# Sheet11.net
KiCad netlist of a schematic drawn in Altium Designer
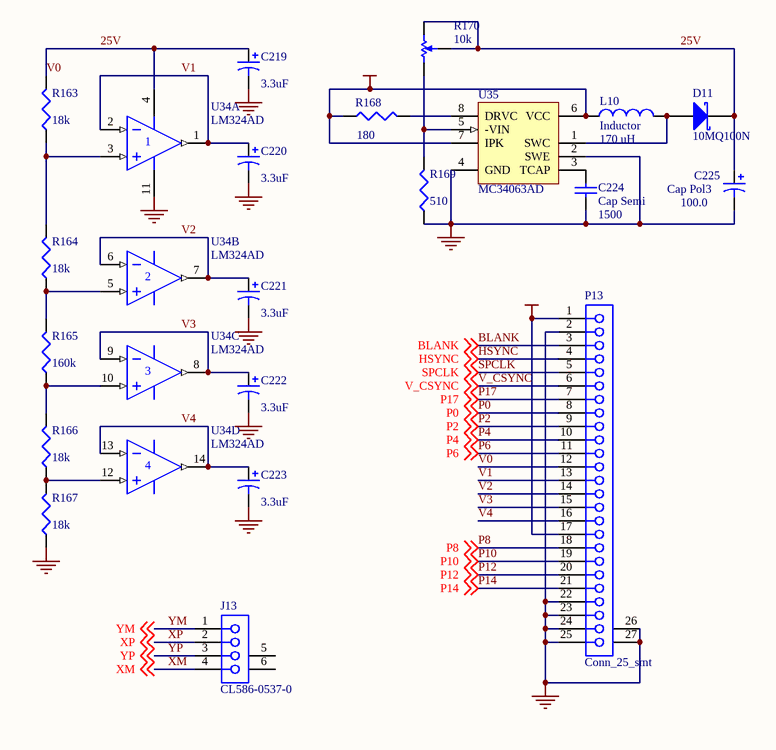
[diagram p0: Sheet11.SchDoc]

(export (version "E")
  (design (tool "Eeschema 10.0.6"))
  (components
    (comp (ref "C219")
      (value "3.3uF")
      (footprint "CC2012-0805")
      (description "Polarized Capacitor (Surface Mount)")
      (fields (field (name "Comment") "Cap Pol3") (field (name "PUBLISHER") "Altium Limited"))
      (libsource (lib "Miscellaneous Devices") (part "Cap Pol3"))
    )
    (comp (ref "C220")
      (value "3.3uF")
      (footprint "CC2012-0805")
      (description "Polarized Capacitor (Surface Mount)")
      (fields (field (name "Comment") "Cap Pol3") (field (name "PUBLISHER") "Altium Limited"))
      (libsource (lib "Miscellaneous Devices") (part "Cap Pol3"))
    )
    (comp (ref "C221")
      (value "3.3uF")
      (footprint "CC2012-0805")
      (description "Polarized Capacitor (Surface Mount)")
      (fields (field (name "Comment") "Cap Pol3") (field (name "PUBLISHER") "Altium Limited"))
      (libsource (lib "Miscellaneous Devices") (part "Cap Pol3"))
    )
    (comp (ref "C222")
      (value "3.3uF")
      (footprint "CC2012-0805")
      (description "Polarized Capacitor (Surface Mount)")
      (fields (field (name "Comment") "Cap Pol3") (field (name "PUBLISHER") "Altium Limited"))
      (libsource (lib "Miscellaneous Devices") (part "Cap Pol3"))
    )
    (comp (ref "C223")
      (value "3.3uF")
      (footprint "CC2012-0805")
      (description "Polarized Capacitor (Surface Mount)")
      (fields (field (name "Comment") "Cap Pol3") (field (name "PUBLISHER") "Altium Limited"))
      (libsource (lib "Miscellaneous Devices") (part "Cap Pol3"))
    )
    (comp (ref "C224")
      (value "Cap Semi")
      (footprint "CC1608-0603")
      (description "Capacitor (Semiconductor SIM Model)")
      (fields (field (name "ALTIUM_VALUE") "1500") (field (name "PUBLISHER") "Altium Limited"))
      (libsource (lib "Miscellaneous Devices") (part "Cap Semi"))
    )
    (comp (ref "C225")
      (value "Cap Pol3")
      (footprint "CC5664-2225")
      (description "Polarized Capacitor (Surface Mount)")
      (fields (field (name "ALTIUM_VALUE") "100.0") (field (name "PUBLISHER") "Altium Limited"))
      (libsource (lib "Miscellaneous Devices") (part "Cap Pol3"))
    )
    (comp (ref "D11")
      (value "10MQ100N")
      (footprint "CD4532-1812")
      (description "Schottky Diode")
      (fields (field (name "PUBLISHER") "Altium Limited"))
      (libsource (lib "Miscellaneous Devices") (part "D Schottky"))
    )
    (comp (ref "J13")
      (value "CL586-0537-0")
      (footprint "FH12-10(4)SA-1SH")
      (description "FH12 Series, \"Flip-Lock\" SMT/ZIF Connector - 1.0mm Spaced Bottom Eccentric Contact")
      (fields (field (name "PUBLISHER") "Altium Limited"))
      (libsource (lib "HRS FPC-FFC FH12 Series") (part "CL586-0537-0"))
    )
    (comp (ref "L10")
      (value "Inductor")
      (footprint "INDC4532-1812")
      (fields (field (name "ALTIUM_VALUE") "170 uH") (field (name "PUBLISHER") "Altium Limited"))
      (libsource (lib "Miscellaneous Devices") (part "Inductor"))
    )
    (comp (ref "P13")
      (value "Conn_25_smt")
      (footprint "Conn_25_smt")
      (libsource (lib "connectors") (part "Conn_25_smt"))
    )
    (comp (ref "R163")
      (value "18k")
      (footprint "CR1608-0603")
      (description "Resistor")
      (fields (field (name "Comment") "Res3") (field (name "PUBLISHER") "Altium Limited"))
      (libsource (lib "Miscellaneous Devices") (part "Res3"))
    )
    (comp (ref "R164")
      (value "18k")
      (footprint "CR1608-0603")
      (description "Resistor")
      (fields (field (name "Comment") "Res3") (field (name "PUBLISHER") "Altium Limited"))
      (libsource (lib "Miscellaneous Devices") (part "Res3"))
    )
    (comp (ref "R165")
      (value "160k")
      (footprint "CR1608-0603")
      (description "Resistor")
      (fields (field (name "Comment") "Res3") (field (name "PUBLISHER") "Altium Limited"))
      (libsource (lib "Miscellaneous Devices") (part "Res3"))
    )
    (comp (ref "R166")
      (value "18k")
      (footprint "CR1608-0603")
      (description "Resistor")
      (fields (field (name "Comment") "Res3") (field (name "PUBLISHER") "Altium Limited"))
      (libsource (lib "Miscellaneous Devices") (part "Res3"))
    )
    (comp (ref "R167")
      (value "18k")
      (footprint "CR1608-0603")
      (description "Resistor")
      (fields (field (name "Comment") "Res3") (field (name "PUBLISHER") "Altium Limited"))
      (libsource (lib "Miscellaneous Devices") (part "Res3"))
    )
    (comp (ref "R168")
      (value "180")
      (footprint "CR1608-0603")
      (description "Resistor")
      (fields (field (name "Comment") "Res3") (field (name "PUBLISHER") "Altium Limited"))
      (libsource (lib "Miscellaneous Devices") (part "Res3"))
    )
    (comp (ref "R169")
      (value "510")
      (footprint "CR1608-0603")
      (description "Resistor")
      (fields (field (name "Comment") "Res3") (field (name "PUBLISHER") "Altium Limited"))
      (libsource (lib "Miscellaneous Devices") (part "Res3"))
    )
    (comp (ref "R170")
      (value "10k")
      (footprint "POT4MM-2")
      (description "Square Trimming Potentiometer")
      (fields (field (name "PUBLISHER") "Altium Limited"))
      (libsource (lib "Miscellaneous Devices") (part "RPot SM"))
    )
    (comp (ref "U34")
      (value "LM324AD")
      (footprint "751A-02")
      (description "Quad Low-Power Operational Amplifier")
      (fields (field (name "PUBLISHER") "Altium Limited"))
      (libsource (lib "Motorola Amplifier Operational Amplifier") (part "LM324AD"))
    )
    (comp (ref "U35")
      (value "MC34063AD")
      (footprint "751-02")
      (description "DC-to-DC Converter Control Circuit")
      (fields (field (name "PUBLISHER") "Altium Limited"))
      (libsource (lib "Motorola Power Mgt DC-DC Converter") (part "MC34063AD"))
    )
  )
  (nets
    (net (code "1") (name "/V1") (class "Default")
      (node (ref "C220") (pin "1") (pinfunction "1_1") (pintype "passive"))
      (node (ref "P13") (pin "13") (pinfunction "13_13") (pintype "passive"))
      (node (ref "U34") (pin "1") (pinfunction "OUT_1") (pintype "output"))
      (node (ref "U34") (pin "2") (pinfunction "IN-_2") (pintype "input"))
    )
    (net (code "2") (name "/V2") (class "Default")
      (node (ref "C221") (pin "1") (pinfunction "1_1") (pintype "passive"))
      (node (ref "P13") (pin "14") (pinfunction "14_14") (pintype "passive"))
      (node (ref "U34") (pin "6") (pinfunction "IN-_6") (pintype "input"))
      (node (ref "U34") (pin "7") (pinfunction "OUT_7") (pintype "output"))
    )
    (net (code "3") (name "/V3") (class "Default")
      (node (ref "C222") (pin "1") (pinfunction "1_1") (pintype "passive"))
      (node (ref "P13") (pin "15") (pinfunction "15_15") (pintype "passive"))
      (node (ref "U34") (pin "8") (pinfunction "OUT_8") (pintype "output"))
      (node (ref "U34") (pin "9") (pinfunction "IN-_9") (pintype "input"))
    )
    (net (code "4") (name "/V4") (class "Default")
      (node (ref "C223") (pin "1") (pinfunction "1_1") (pintype "passive"))
      (node (ref "P13") (pin "16") (pinfunction "16_16") (pintype "passive"))
      (node (ref "U34") (pin "13") (pinfunction "IN-_13") (pintype "input"))
      (node (ref "U34") (pin "14") (pinfunction "OUT_14") (pintype "output"))
    )
    (net (code "5") (name "BLANK") (class "Default")
      (node (ref "P13") (pin "3") (pinfunction "3_3") (pintype "passive"))
    )
    (net (code "6") (name "GND") (class "Default")
      (node (ref "C219") (pin "2") (pinfunction "2_2") (pintype "passive"))
      (node (ref "C220") (pin "2") (pinfunction "2_2") (pintype "passive"))
      (node (ref "C221") (pin "2") (pinfunction "2_2") (pintype "passive"))
      (node (ref "C222") (pin "2") (pinfunction "2_2") (pintype "passive"))
      (node (ref "C223") (pin "2") (pinfunction "2_2") (pintype "passive"))
      (node (ref "C224") (pin "1") (pinfunction "1_1") (pintype "passive"))
      (node (ref "C225") (pin "2") (pinfunction "2_2") (pintype "passive"))
      (node (ref "P13") (pin "2") (pinfunction "2_2") (pintype "passive"))
      (node (ref "P13") (pin "22") (pinfunction "22_22") (pintype "passive"))
      (node (ref "P13") (pin "23") (pinfunction "23_23") (pintype "passive"))
      (node (ref "P13") (pin "24") (pinfunction "24_24") (pintype "passive"))
      (node (ref "P13") (pin "25") (pinfunction "25_25") (pintype "passive"))
      (node (ref "P13") (pin "26") (pinfunction "MH1_26") (pintype "passive"))
      (node (ref "P13") (pin "27") (pinfunction "MH2_27") (pintype "passive"))
      (node (ref "R167") (pin "1") (pinfunction "1_1") (pintype "passive"))
      (node (ref "R169") (pin "1") (pinfunction "1_1") (pintype "passive"))
      (node (ref "U34") (pin "11") (pinfunction "V-_11") (pintype "power_in"))
      (node (ref "U35") (pin "2") (pinfunction "SWE_2") (pintype "open_emitter"))
      (node (ref "U35") (pin "4") (pinfunction "GND_4") (pintype "power_in"))
    )
    (net (code "7") (name "HSYNC") (class "Default")
      (node (ref "P13") (pin "4") (pinfunction "4_4") (pintype "passive"))
    )
    (net (code "8") (name "Net-(D11-A)") (class "Default")
      (node (ref "D11") (pin "1") (pinfunction "A_1") (pintype "passive"))
      (node (ref "L10") (pin "2") (pinfunction "2_2") (pintype "passive"))
      (node (ref "U35") (pin "1") (pinfunction "SWC_1") (pintype "open_collector"))
    )
    (net (code "9") (name "Net-(R170--)") (class "Default")
      (node (ref "R169") (pin "2") (pinfunction "2_2") (pintype "passive"))
      (node (ref "R170") (pin "CCW") (pinfunction "-_CCW") (pintype "passive"))
      (node (ref "U35") (pin "5") (pinfunction "-VIN_5") (pintype "input"))
    )
    (net (code "10") (name "Net-(U34A-IN+)") (class "Default")
      (node (ref "R163") (pin "1") (pinfunction "1_1") (pintype "passive"))
      (node (ref "R164") (pin "2") (pinfunction "2_2") (pintype "passive"))
      (node (ref "U34") (pin "3") (pinfunction "IN+_3") (pintype "input"))
    )
    (net (code "11") (name "Net-(U34B-IN+)") (class "Default")
      (node (ref "R164") (pin "1") (pinfunction "1_1") (pintype "passive"))
      (node (ref "R165") (pin "2") (pinfunction "2_2") (pintype "passive"))
      (node (ref "U34") (pin "5") (pinfunction "IN+_5") (pintype "input"))
    )
    (net (code "12") (name "Net-(U34C-IN+)") (class "Default")
      (node (ref "R165") (pin "1") (pinfunction "1_1") (pintype "passive"))
      (node (ref "R166") (pin "2") (pinfunction "2_2") (pintype "passive"))
      (node (ref "U34") (pin "10") (pinfunction "IN+_10") (pintype "input"))
    )
    (net (code "13") (name "Net-(U34D-IN+)") (class "Default")
      (node (ref "R166") (pin "1") (pinfunction "1_1") (pintype "passive"))
      (node (ref "R167") (pin "2") (pinfunction "2_2") (pintype "passive"))
      (node (ref "U34") (pin "12") (pinfunction "IN+_12") (pintype "input"))
    )
    (net (code "14") (name "Net-(U35-DRVC)") (class "Default")
      (node (ref "R168") (pin "2") (pinfunction "2_2") (pintype "passive"))
      (node (ref "U35") (pin "8") (pinfunction "DRVC_8") (pintype "open_collector"))
    )
    (net (code "15") (name "Net-(U35-TCAP)") (class "Default")
      (node (ref "C224") (pin "2") (pinfunction "2_2") (pintype "passive"))
      (node (ref "U35") (pin "3") (pinfunction "TCAP_3") (pintype "passive"))
    )
    (net (code "16") (name "P0") (class "Default")
      (node (ref "P13") (pin "8") (pinfunction "8_8") (pintype "passive"))
    )
    (net (code "17") (name "P2") (class "Default")
      (node (ref "P13") (pin "9") (pinfunction "9_9") (pintype "passive"))
    )
    (net (code "18") (name "P4") (class "Default")
      (node (ref "P13") (pin "10") (pinfunction "10_10") (pintype "passive"))
    )
    (net (code "19") (name "P6") (class "Default")
      (node (ref "P13") (pin "11") (pinfunction "11_11") (pintype "passive"))
    )
    (net (code "20") (name "P8") (class "Default")
      (node (ref "P13") (pin "18") (pinfunction "18_18") (pintype "passive"))
    )
    (net (code "21") (name "P10") (class "Default")
      (node (ref "P13") (pin "19") (pinfunction "19_19") (pintype "passive"))
    )
    (net (code "22") (name "P12") (class "Default")
      (node (ref "P13") (pin "20") (pinfunction "20_20") (pintype "passive"))
    )
    (net (code "23") (name "P14") (class "Default")
      (node (ref "P13") (pin "21") (pinfunction "21_21") (pintype "passive"))
    )
    (net (code "24") (name "P17") (class "Default")
      (node (ref "P13") (pin "7") (pinfunction "7_7") (pintype "passive"))
    )
    (net (code "25") (name "SPCLK") (class "Default")
      (node (ref "P13") (pin "5") (pinfunction "5_5") (pintype "passive"))
    )
    (net (code "26") (name "V+") (class "Default")
      (node (ref "C219") (pin "1") (pinfunction "1_1") (pintype "passive"))
      (node (ref "C225") (pin "1") (pinfunction "1_1") (pintype "passive"))
      (node (ref "D11") (pin "2") (pinfunction "K_2") (pintype "passive"))
      (node (ref "P13") (pin "12") (pinfunction "12_12") (pintype "passive"))
      (node (ref "R163") (pin "2") (pinfunction "2_2") (pintype "passive"))
      (node (ref "R170") (pin "CW") (pinfunction "+_CW") (pintype "passive"))
      (node (ref "R170") (pin "W") (pinfunction "W_W") (pintype "passive"))
      (node (ref "U34") (pin "4") (pinfunction "V+_4") (pintype "power_in"))
    )
    (net (code "27") (name "VCC12") (class "Default")
      (node (ref "L10") (pin "1") (pinfunction "1_1") (pintype "passive"))
      (node (ref "R168") (pin "1") (pinfunction "1_1") (pintype "passive"))
      (node (ref "U35") (pin "6") (pinfunction "VCC_6") (pintype "power_in"))
      (node (ref "U35") (pin "7") (pinfunction "IPK_7") (pintype "passive"))
    )
    (net (code "28") (name "VCCIO") (class "Default")
      (node (ref "P13") (pin "1") (pinfunction "1_1") (pintype "passive"))
      (node (ref "P13") (pin "17") (pinfunction "17_17") (pintype "passive"))
    )
    (net (code "29") (name "V_CSYNC") (class "Default")
      (node (ref "P13") (pin "6") (pinfunction "6_6") (pintype "passive"))
    )
    (net (code "30") (name "XM") (class "Default")
      (node (ref "J13") (pin "4") (pinfunction "4_4") (pintype "passive"))
    )
    (net (code "31") (name "XP") (class "Default")
      (node (ref "J13") (pin "2") (pinfunction "2_2") (pintype "passive"))
    )
    (net (code "32") (name "YM") (class "Default")
      (node (ref "J13") (pin "1") (pinfunction "1_1") (pintype "passive"))
    )
    (net (code "33") (name "YP") (class "Default")
      (node (ref "J13") (pin "3") (pinfunction "3_3") (pintype "passive"))
    )
    (net (code "34") (name "unconnected-(J13-MH1-Pad5)") (class "Default")
      (node (ref "J13") (pin "5") (pinfunction "MH1_5") (pintype "passive"))
    )
    (net (code "35") (name "unconnected-(J13-MH2-Pad6)") (class "Default")
      (node (ref "J13") (pin "6") (pinfunction "MH2_6") (pintype "passive"))
    )
  )
)
